# TP_STD_PERIPHERALS.net
KiCad netlist of a schematic drawn in Altium Designer
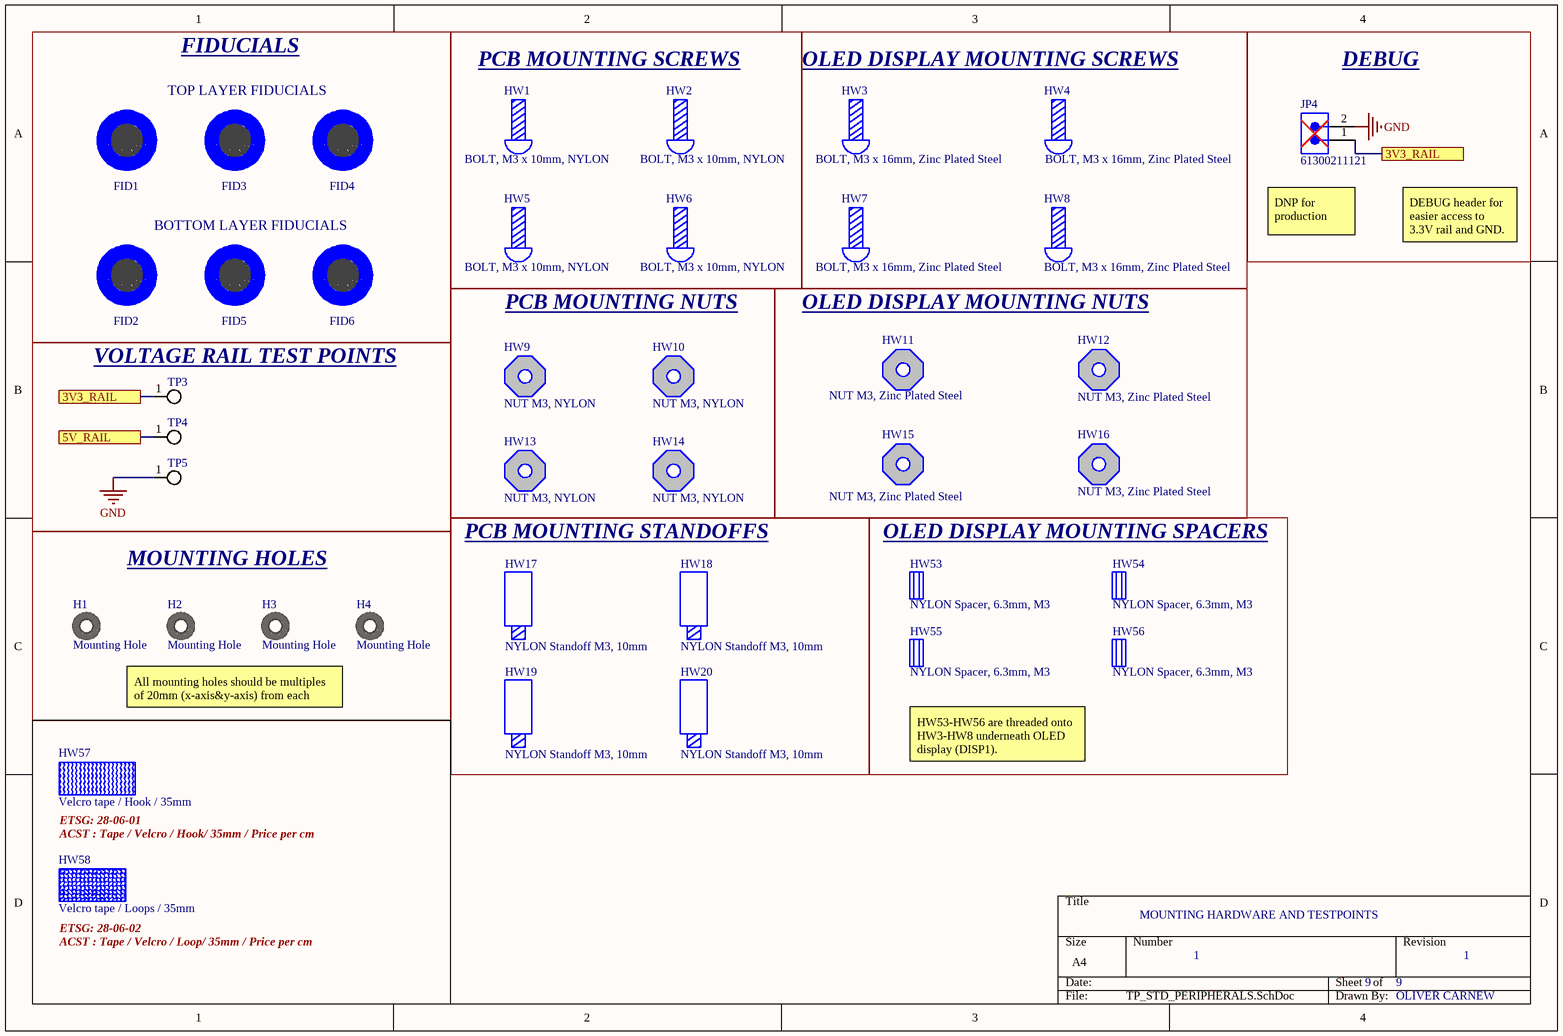
[diagram p0: TP_STD_PERIPHERALS.SchDoc]

(export (version "E")
  (design (tool "Eeschema 10.0.6"))
  (components
    (comp (ref "FID1")
      (value "Fiducial Mark")
      (footprint "FIDUCIAL_SMALL")
      (description "Small 1mm/40mil pad with 40mm soldermask clearance")
      (libsource (lib "DANCE_LIB_REV2") (part "FIDUCIAL_SMALL"))
    )
    (comp (ref "FID2")
      (value "Fiducial Mark")
      (footprint "FIDUCIAL_SMALL")
      (description "Small 1mm/40mil pad with 40mm soldermask clearance")
      (libsource (lib "DANCE_LIB_REV2") (part "FIDUCIAL_SMALL"))
    )
    (comp (ref "FID3")
      (value "Fiducial Mark")
      (footprint "FIDUCIAL_SMALL")
      (description "Small 1mm/40mil pad with 40mm soldermask clearance")
      (libsource (lib "DANCE_LIB_REV2") (part "FIDUCIAL_SMALL"))
    )
    (comp (ref "FID4")
      (value "Fiducial Mark")
      (footprint "FIDUCIAL_SMALL")
      (description "Small 1mm/40mil pad with 40mm soldermask clearance")
      (libsource (lib "DANCE_LIB_REV2") (part "FIDUCIAL_SMALL"))
    )
    (comp (ref "FID5")
      (value "Fiducial Mark")
      (footprint "FIDUCIAL_SMALL")
      (description "Small 1mm/40mil pad with 40mm soldermask clearance")
      (libsource (lib "DANCE_LIB_REV2") (part "FIDUCIAL_SMALL"))
    )
    (comp (ref "FID6")
      (value "Fiducial Mark")
      (footprint "FIDUCIAL_SMALL")
      (description "Small 1mm/40mil pad with 40mm soldermask clearance")
      (libsource (lib "DANCE_LIB_REV2") (part "FIDUCIAL_SMALL"))
    )
    (comp (ref "H1")
      (value "Mounting Hole")
      (footprint "M3_MOUNTING_HOLE_3_4_mm")
      (description "M3 Mounting hole (3.4mm)")
      (libsource (lib "DANCE_LIB_REV2") (part "M3_MOUNTING_HOLE"))
    )
    (comp (ref "H2")
      (value "Mounting Hole")
      (footprint "M3_MOUNTING_HOLE_3_4_mm")
      (description "M3 Mounting hole (3.4mm)")
      (libsource (lib "DANCE_LIB_REV2") (part "M3_MOUNTING_HOLE"))
    )
    (comp (ref "H3")
      (value "Mounting Hole")
      (footprint "M3_MOUNTING_HOLE_3_4_mm")
      (description "M3 Mounting hole (3.4mm)")
      (libsource (lib "DANCE_LIB_REV2") (part "M3_MOUNTING_HOLE"))
    )
    (comp (ref "H4")
      (value "Mounting Hole")
      (footprint "M3_MOUNTING_HOLE_3_4_mm")
      (description "M3 Mounting hole (3.4mm)")
      (libsource (lib "DANCE_LIB_REV2") (part "M3_MOUNTING_HOLE"))
    )
    (comp (ref "HW1") (value "BOLT, M3 x 10mm, NYLON") (libsource (lib "DANCE_LIB_REV2") (part "M3_SCREW")))
    (comp (ref "HW2") (value "BOLT, M3 x 10mm, NYLON") (libsource (lib "DANCE_LIB_REV2") (part "M3_SCREW")))
    (comp (ref "HW3")
      (value "BOLT, M3 x 16mm, Zinc Plated Steel")
      (libsource (lib "DANCE_LIB_REV2") (part "M3_SCREW"))
    )
    (comp (ref "HW4")
      (value "BOLT, M3 x 16mm, Zinc Plated Steel")
      (libsource (lib "DANCE_LIB_REV2") (part "M3_SCREW"))
    )
    (comp (ref "HW5") (value "BOLT, M3 x 10mm, NYLON") (libsource (lib "DANCE_LIB_REV2") (part "M3_SCREW")))
    (comp (ref "HW6") (value "BOLT, M3 x 10mm, NYLON") (libsource (lib "DANCE_LIB_REV2") (part "M3_SCREW")))
    (comp (ref "HW7")
      (value "BOLT, M3 x 16mm, Zinc Plated Steel")
      (libsource (lib "DANCE_LIB_REV2") (part "M3_SCREW"))
    )
    (comp (ref "HW8")
      (value "BOLT, M3 x 16mm, Zinc Plated Steel")
      (libsource (lib "DANCE_LIB_REV2") (part "M3_SCREW"))
    )
    (comp (ref "HW9") (value "NUT M3, NYLON") (libsource (lib "DANCE_LIB_REV2") (part "NUT")))
    (comp (ref "HW10") (value "NUT M3, NYLON") (libsource (lib "DANCE_LIB_REV2") (part "NUT")))
    (comp (ref "HW11") (value "NUT M3, Zinc Plated Steel") (libsource (lib "DANCE_LIB_REV2") (part "NUT")))
    (comp (ref "HW12") (value "NUT M3, Zinc Plated Steel") (libsource (lib "DANCE_LIB_REV2") (part "NUT")))
    (comp (ref "HW13") (value "NUT M3, NYLON") (libsource (lib "DANCE_LIB_REV2") (part "NUT")))
    (comp (ref "HW14") (value "NUT M3, NYLON") (libsource (lib "DANCE_LIB_REV2") (part "NUT")))
    (comp (ref "HW15") (value "NUT M3, Zinc Plated Steel") (libsource (lib "DANCE_LIB_REV2") (part "NUT")))
    (comp (ref "HW16") (value "NUT M3, Zinc Plated Steel") (libsource (lib "DANCE_LIB_REV2") (part "NUT")))
    (comp (ref "HW17") (value "NYLON Standoff M3, 10mm") (libsource (lib "DANCE_LIB_REV2") (part "STANDOFF")))
    (comp (ref "HW18") (value "NYLON Standoff M3, 10mm") (libsource (lib "DANCE_LIB_REV2") (part "STANDOFF")))
    (comp (ref "HW19") (value "NYLON Standoff M3, 10mm") (libsource (lib "DANCE_LIB_REV2") (part "STANDOFF")))
    (comp (ref "HW20") (value "NYLON Standoff M3, 10mm") (libsource (lib "DANCE_LIB_REV2") (part "STANDOFF")))
    (comp (ref "HW53")
      (value "NYLON Spacer, 6.3mm, M3")
      (description "Spacer / Female - Female / Nylon / Hexagonal / M3 x 06.3")
      (libsource (lib "DANCE_LIB_REV2") (part "NYLON_STANDOFF_6_3_mm"))
    )
    (comp (ref "HW54")
      (value "NYLON Spacer, 6.3mm, M3")
      (description "Spacer / Female - Female / Nylon / Hexagonal / M3 x 06.3")
      (libsource (lib "DANCE_LIB_REV2") (part "NYLON_STANDOFF_6_3_mm"))
    )
    (comp (ref "HW55")
      (value "NYLON Spacer, 6.3mm, M3")
      (description "Spacer / Female - Female / Nylon / Hexagonal / M3 x 06.3")
      (libsource (lib "DANCE_LIB_REV2") (part "NYLON_STANDOFF_6_3_mm"))
    )
    (comp (ref "HW56")
      (value "NYLON Spacer, 6.3mm, M3")
      (description "Spacer / Female - Female / Nylon / Hexagonal / M3 x 06.3")
      (libsource (lib "DANCE_LIB_REV2") (part "NYLON_STANDOFF_6_3_mm"))
    )
    (comp (ref "HW57")
      (value "Velcro tape / Hook / 35mm")
      (description "ETSG: 28-06-01\r\nACST : Tape / Velcro / Hook \r\n/ 20mm / Price per cm")
      (libsource (lib "DANCE_LIB_REV2") (part "VELCRO_HOOKS"))
    )
    (comp (ref "HW58")
      (value "Velcro tape / Loops / 35mm")
      (description "ETSG: 28-06-01\r\nACST : Tape / Velcro / Hook\r\n/ 20mm / Price per cm")
      (libsource (lib "DANCE_LIB_REV2") (part "VELCRO_LOOP"))
    )
    (comp (ref "JP4")
      (value "61300211121")
      (footprint "61300211121")
      (libsource (lib "Altium Content Vault") (part "Header_Male_1R_02P"))
    )
    (comp (ref "TP3")
      (value "Small testpoint 40mil")
      (footprint "TEST_POINT_SMALL")
      (description "40mil circular pad no hole")
      (libsource (lib "DANCE_LIB_REV2") (part "TEST_POINT_SMALL"))
    )
    (comp (ref "TP4")
      (value "Small testpoint 40mil")
      (footprint "TEST_POINT_SMALL")
      (description "40mil circular pad no hole")
      (libsource (lib "DANCE_LIB_REV2") (part "TEST_POINT_SMALL"))
    )
    (comp (ref "TP5")
      (value "Small testpoint 40mil")
      (footprint "TEST_POINT_SMALL")
      (description "40mil circular pad no hole")
      (libsource (lib "DANCE_LIB_REV2") (part "TEST_POINT_SMALL"))
    )
  )
  (nets
    (net (code "1") (name "/3V3_RAIL") (class "Default")
      (node (ref "JP4") (pin "1") (pinfunction "1_1") (pintype "passive"))
      (node (ref "TP3") (pin "1") (pinfunction "1_1") (pintype "passive"))
    )
    (net (code "2") (name "/5V_RAIL") (class "Default")
      (node (ref "TP4") (pin "1") (pinfunction "1_1") (pintype "passive"))
    )
    (net (code "3") (name "GND") (class "Default")
      (node (ref "JP4") (pin "2") (pinfunction "2_2") (pintype "passive"))
      (node (ref "TP5") (pin "1") (pinfunction "1_1") (pintype "passive"))
    )
  )
)
